# Supplies.net
KiCad netlist of a schematic drawn in Altium Designer
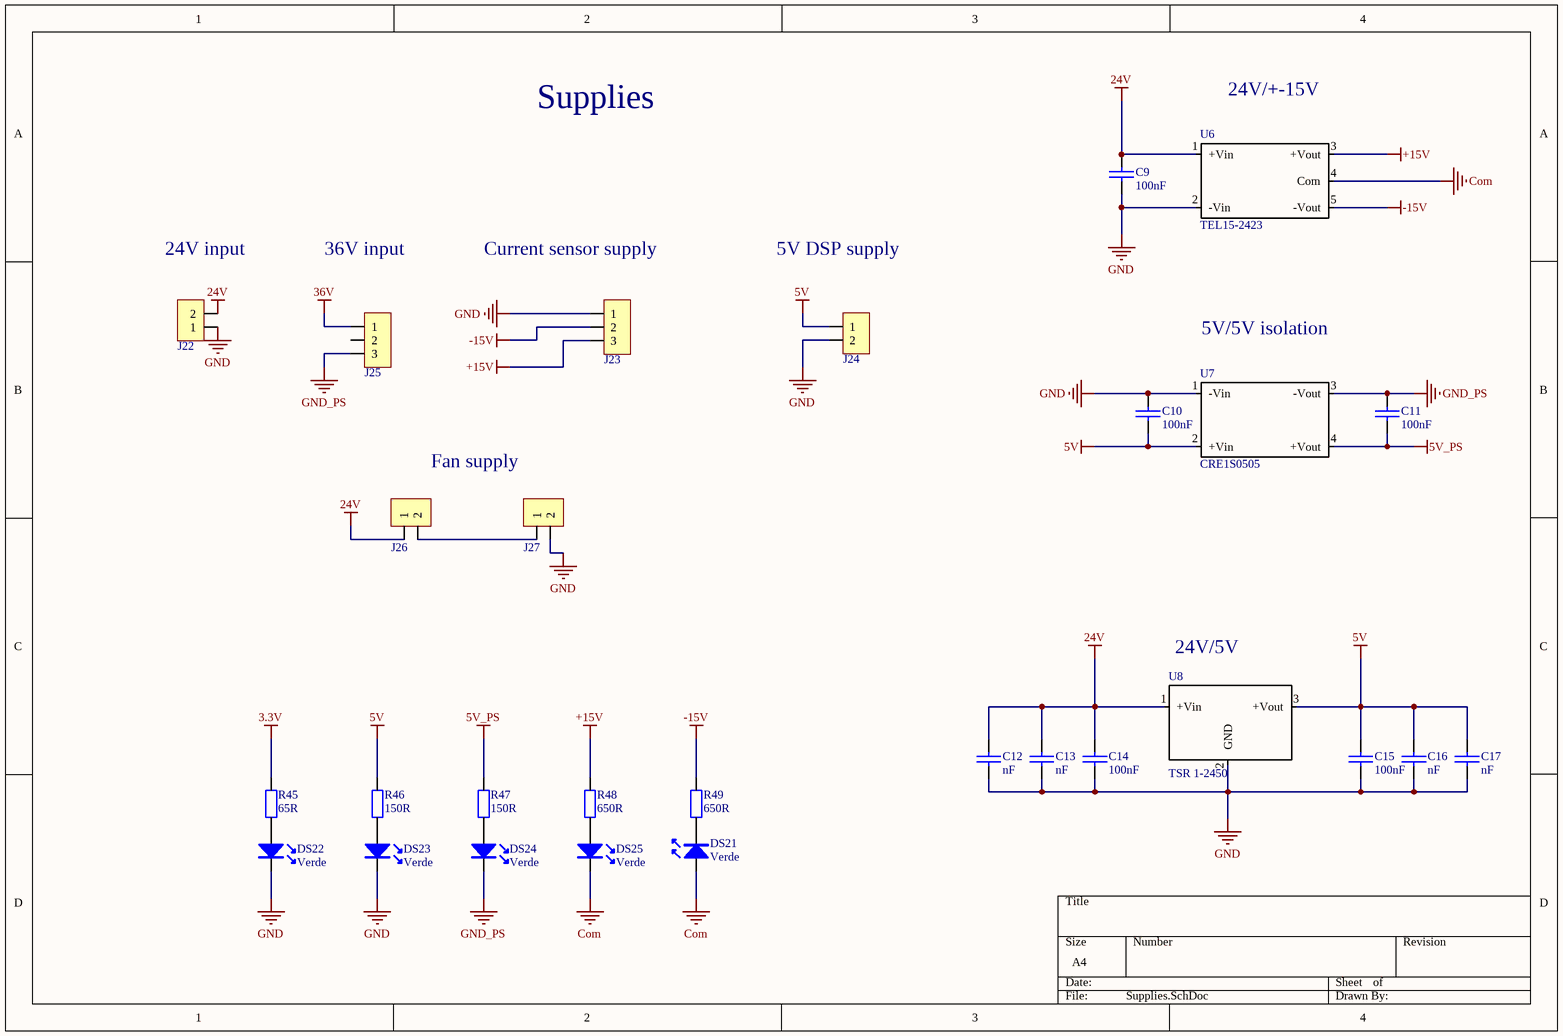
[diagram p0: Supplies.SchDoc]

(export (version "E")
  (design (tool "Eeschema 10.0.6"))
  (components
    (comp (ref "C9")
      (value "100nF")
      (footprint "1206")
      (description "Condensador")
      (libsource (lib "SCH_Lib") (part "Condensador"))
    )
    (comp (ref "C10")
      (value "100nF")
      (footprint "1206")
      (description "Condensador")
      (libsource (lib "SCH_Lib") (part "Condensador"))
    )
    (comp (ref "C11")
      (value "100nF")
      (footprint "1206")
      (description "Condensador")
      (libsource (lib "SCH_Lib") (part "Condensador"))
    )
    (comp (ref "C12")
      (value "nF")
      (footprint "1206")
      (description "Condensador")
      (libsource (lib "SCH_Lib") (part "Condensador"))
    )
    (comp (ref "C13")
      (value "nF")
      (footprint "1206")
      (description "Condensador")
      (libsource (lib "SCH_Lib") (part "Condensador"))
    )
    (comp (ref "C14")
      (value "100nF")
      (footprint "1206")
      (description "Condensador")
      (libsource (lib "SCH_Lib") (part "Condensador"))
    )
    (comp (ref "C15")
      (value "100nF")
      (footprint "1206")
      (description "Condensador")
      (libsource (lib "SCH_Lib") (part "Condensador"))
    )
    (comp (ref "C16")
      (value "nF")
      (footprint "1206")
      (description "Condensador")
      (libsource (lib "SCH_Lib") (part "Condensador"))
    )
    (comp (ref "C17")
      (value "nF")
      (footprint "1206")
      (description "Condensador")
      (libsource (lib "SCH_Lib") (part "Condensador"))
    )
    (comp (ref "DS21") (value "Verde") (footprint "LED_100mil") (libsource (lib "SCH_Lib") (part "Led")))
    (comp (ref "DS22") (value "Verde") (footprint "LED_100mil") (libsource (lib "SCH_Lib") (part "Led")))
    (comp (ref "DS23") (value "Verde") (footprint "LED_100mil") (libsource (lib "SCH_Lib") (part "Led")))
    (comp (ref "DS24") (value "Verde") (footprint "LED_100mil") (libsource (lib "SCH_Lib") (part "Led")))
    (comp (ref "DS25") (value "Verde") (footprint "LED_100mil") (libsource (lib "SCH_Lib") (part "Led")))
    (comp (ref "J22")
      (value "Cleva 2 vias")
      (footprint "Con2_ExtronSide_3.5mmPitch")
      (libsource (lib "SCH_Lib") (part "Con_2"))
    )
    (comp (ref "J23")
      (value "Cur_meas_con")
      (footprint "Con3_KK_256")
      (libsource (lib "SCH_Lib") (part "Con_3"))
    )
    (comp (ref "J24") (value "Cleva 2 vias") (footprint "Clema_2_vias") (libsource (lib "") (part "Con_2_2")))
    (comp (ref "J25")
      (value "Cleva 2 vias")
      (footprint "Con3_150milPitch")
      (libsource (lib "SCH_Lib") (part "Con_3"))
    )
    (comp (ref "J26") (value "Cleva 2 vias") (footprint "Con2_KK_256") (libsource (lib "") (part "Con_2_1")))
    (comp (ref "J27") (value "Cleva 2 vias") (footprint "Con2_KK_256") (libsource (lib "") (part "Con_2_1")))
    (comp (ref "R45")
      (value "65R")
      (footprint "1206")
      (description "Resistencia")
      (libsource (lib "SCH_Lib") (part "Resistencia"))
    )
    (comp (ref "R46")
      (value "150R")
      (footprint "1206")
      (description "Resistencia")
      (libsource (lib "SCH_Lib") (part "Resistencia"))
    )
    (comp (ref "R47")
      (value "150R")
      (footprint "1206")
      (description "Resistencia")
      (libsource (lib "SCH_Lib") (part "Resistencia"))
    )
    (comp (ref "R48")
      (value "650R")
      (footprint "1206")
      (description "Resistencia")
      (libsource (lib "SCH_Lib") (part "Resistencia"))
    )
    (comp (ref "R49")
      (value "650R")
      (footprint "1206")
      (description "Resistencia")
      (libsource (lib "SCH_Lib") (part "Resistencia"))
    )
    (comp (ref "U6")
      (value "TEL15-2423")
      (footprint "TEL15-2423")
      (libsource (lib "SCH_Lib") (part "TEL15-2423"))
    )
    (comp (ref "U7")
      (value "CRE1S0505")
      (footprint "CRE1S0505SC")
      (libsource (lib "SCH_Lib") (part "CRE1S0505"))
    )
    (comp (ref "U8")
      (value "TSR 1-2450")
      (footprint "TSR 1-2450")
      (libsource (lib "SCH_Lib") (part "TSR 1-2450"))
    )
  )
  (nets
    (net (code "1") (name "+15V") (class "Default")
      (node (ref "J23") (pin "3") (pinfunction "3_3") (pintype "passive"))
      (node (ref "R48") (pin "1") (pinfunction "1_1") (pintype "passive"))
      (node (ref "U6") (pin "3") (pinfunction "+Vout_3") (pintype "passive"))
    )
    (net (code "2") (name "-15V") (class "Default")
      (node (ref "J23") (pin "2") (pinfunction "2_2") (pintype "passive"))
      (node (ref "R49") (pin "1") (pinfunction "1_1") (pintype "passive"))
      (node (ref "U6") (pin "5") (pinfunction "-Vout_5") (pintype "passive"))
    )
    (net (code "3") (name "3.3V") (class "Default")
      (node (ref "R45") (pin "1") (pinfunction "1_1") (pintype "passive"))
    )
    (net (code "4") (name "5V") (class "Default")
      (node (ref "C10") (pin "2") (pintype "passive"))
      (node (ref "C15") (pin "1") (pintype "passive"))
      (node (ref "C16") (pin "1") (pintype "passive"))
      (node (ref "C17") (pin "1") (pintype "passive"))
      (node (ref "J24") (pin "1") (pinfunction "1_1") (pintype "passive"))
      (node (ref "R46") (pin "1") (pinfunction "1_1") (pintype "passive"))
      (node (ref "U7") (pin "2") (pinfunction "+Vin_2") (pintype "passive"))
      (node (ref "U8") (pin "3") (pinfunction "+Vout_3") (pintype "passive"))
    )
    (net (code "5") (name "5V_PS") (class "Default")
      (node (ref "C11") (pin "2") (pintype "passive"))
      (node (ref "R47") (pin "1") (pinfunction "1_1") (pintype "passive"))
      (node (ref "U7") (pin "4") (pinfunction "+Vout_4") (pintype "passive"))
    )
    (net (code "6") (name "24V") (class "Default")
      (node (ref "C12") (pin "1") (pintype "passive"))
      (node (ref "C13") (pin "1") (pintype "passive"))
      (node (ref "C14") (pin "1") (pintype "passive"))
      (node (ref "C9") (pin "1") (pintype "passive"))
      (node (ref "J22") (pin "2") (pinfunction "2_2") (pintype "passive"))
      (node (ref "J26") (pin "1") (pinfunction "1_1") (pintype "passive"))
      (node (ref "U6") (pin "1") (pinfunction "+Vin_1") (pintype "passive"))
      (node (ref "U8") (pin "1") (pinfunction "+Vin_1") (pintype "passive"))
    )
    (net (code "7") (name "36V") (class "Default")
      (node (ref "J25") (pin "1") (pinfunction "1_1") (pintype "passive"))
    )
    (net (code "8") (name "Com") (class "Default")
      (node (ref "DS21") (pin "A") (pinfunction "A_A") (pintype "passive"))
      (node (ref "DS25") (pin "K") (pinfunction "K_K") (pintype "passive"))
      (node (ref "U6") (pin "4") (pinfunction "Com_4") (pintype "passive"))
    )
    (net (code "9") (name "GND") (class "Default")
      (node (ref "C10") (pin "1") (pintype "passive"))
      (node (ref "C12") (pin "2") (pintype "passive"))
      (node (ref "C13") (pin "2") (pintype "passive"))
      (node (ref "C14") (pin "2") (pintype "passive"))
      (node (ref "C15") (pin "2") (pintype "passive"))
      (node (ref "C16") (pin "2") (pintype "passive"))
      (node (ref "C17") (pin "2") (pintype "passive"))
      (node (ref "C9") (pin "2") (pintype "passive"))
      (node (ref "DS22") (pin "K") (pinfunction "K_K") (pintype "passive"))
      (node (ref "DS23") (pin "K") (pinfunction "K_K") (pintype "passive"))
      (node (ref "J22") (pin "1") (pinfunction "1_1") (pintype "passive"))
      (node (ref "J23") (pin "1") (pinfunction "1_1") (pintype "passive"))
      (node (ref "J24") (pin "2") (pinfunction "2_2") (pintype "passive"))
      (node (ref "J27") (pin "2") (pinfunction "2_2") (pintype "passive"))
      (node (ref "U6") (pin "2") (pinfunction "-Vin_2") (pintype "passive"))
      (node (ref "U7") (pin "1") (pinfunction "-Vin_1") (pintype "passive"))
      (node (ref "U8") (pin "2") (pinfunction "GND_2") (pintype "passive"))
    )
    (net (code "10") (name "GND_PS") (class "Default")
      (node (ref "C11") (pin "1") (pintype "passive"))
      (node (ref "DS24") (pin "K") (pinfunction "K_K") (pintype "passive"))
      (node (ref "J25") (pin "3") (pinfunction "3_3") (pintype "passive"))
      (node (ref "U7") (pin "3") (pinfunction "-Vout_3") (pintype "passive"))
    )
    (net (code "11") (name "Net-(DS21-PadK)") (class "Default")
      (node (ref "DS21") (pin "K") (pinfunction "K_K") (pintype "passive"))
      (node (ref "R49") (pin "2") (pinfunction "2_2") (pintype "passive"))
    )
    (net (code "12") (name "Net-(DS22-PadA)") (class "Default")
      (node (ref "DS22") (pin "A") (pinfunction "A_A") (pintype "passive"))
      (node (ref "R45") (pin "2") (pinfunction "2_2") (pintype "passive"))
    )
    (net (code "13") (name "Net-(DS23-PadA)") (class "Default")
      (node (ref "DS23") (pin "A") (pinfunction "A_A") (pintype "passive"))
      (node (ref "R46") (pin "2") (pinfunction "2_2") (pintype "passive"))
    )
    (net (code "14") (name "Net-(DS24-PadA)") (class "Default")
      (node (ref "DS24") (pin "A") (pinfunction "A_A") (pintype "passive"))
      (node (ref "R47") (pin "2") (pinfunction "2_2") (pintype "passive"))
    )
    (net (code "15") (name "Net-(DS25-PadA)") (class "Default")
      (node (ref "DS25") (pin "A") (pinfunction "A_A") (pintype "passive"))
      (node (ref "R48") (pin "2") (pinfunction "2_2") (pintype "passive"))
    )
    (net (code "16") (name "Net-(J26-Pad2)") (class "Default")
      (node (ref "J26") (pin "2") (pinfunction "2_2") (pintype "passive"))
      (node (ref "J27") (pin "1") (pinfunction "1_1") (pintype "passive"))
    )
    (net (code "17") (name "unconnected-(J25-Pad2)") (class "Default")
      (node (ref "J25") (pin "2") (pinfunction "2_2") (pintype "passive"))
    )
  )
)
